# WIFI.net
KiCad netlist of a schematic drawn in Altium Designer
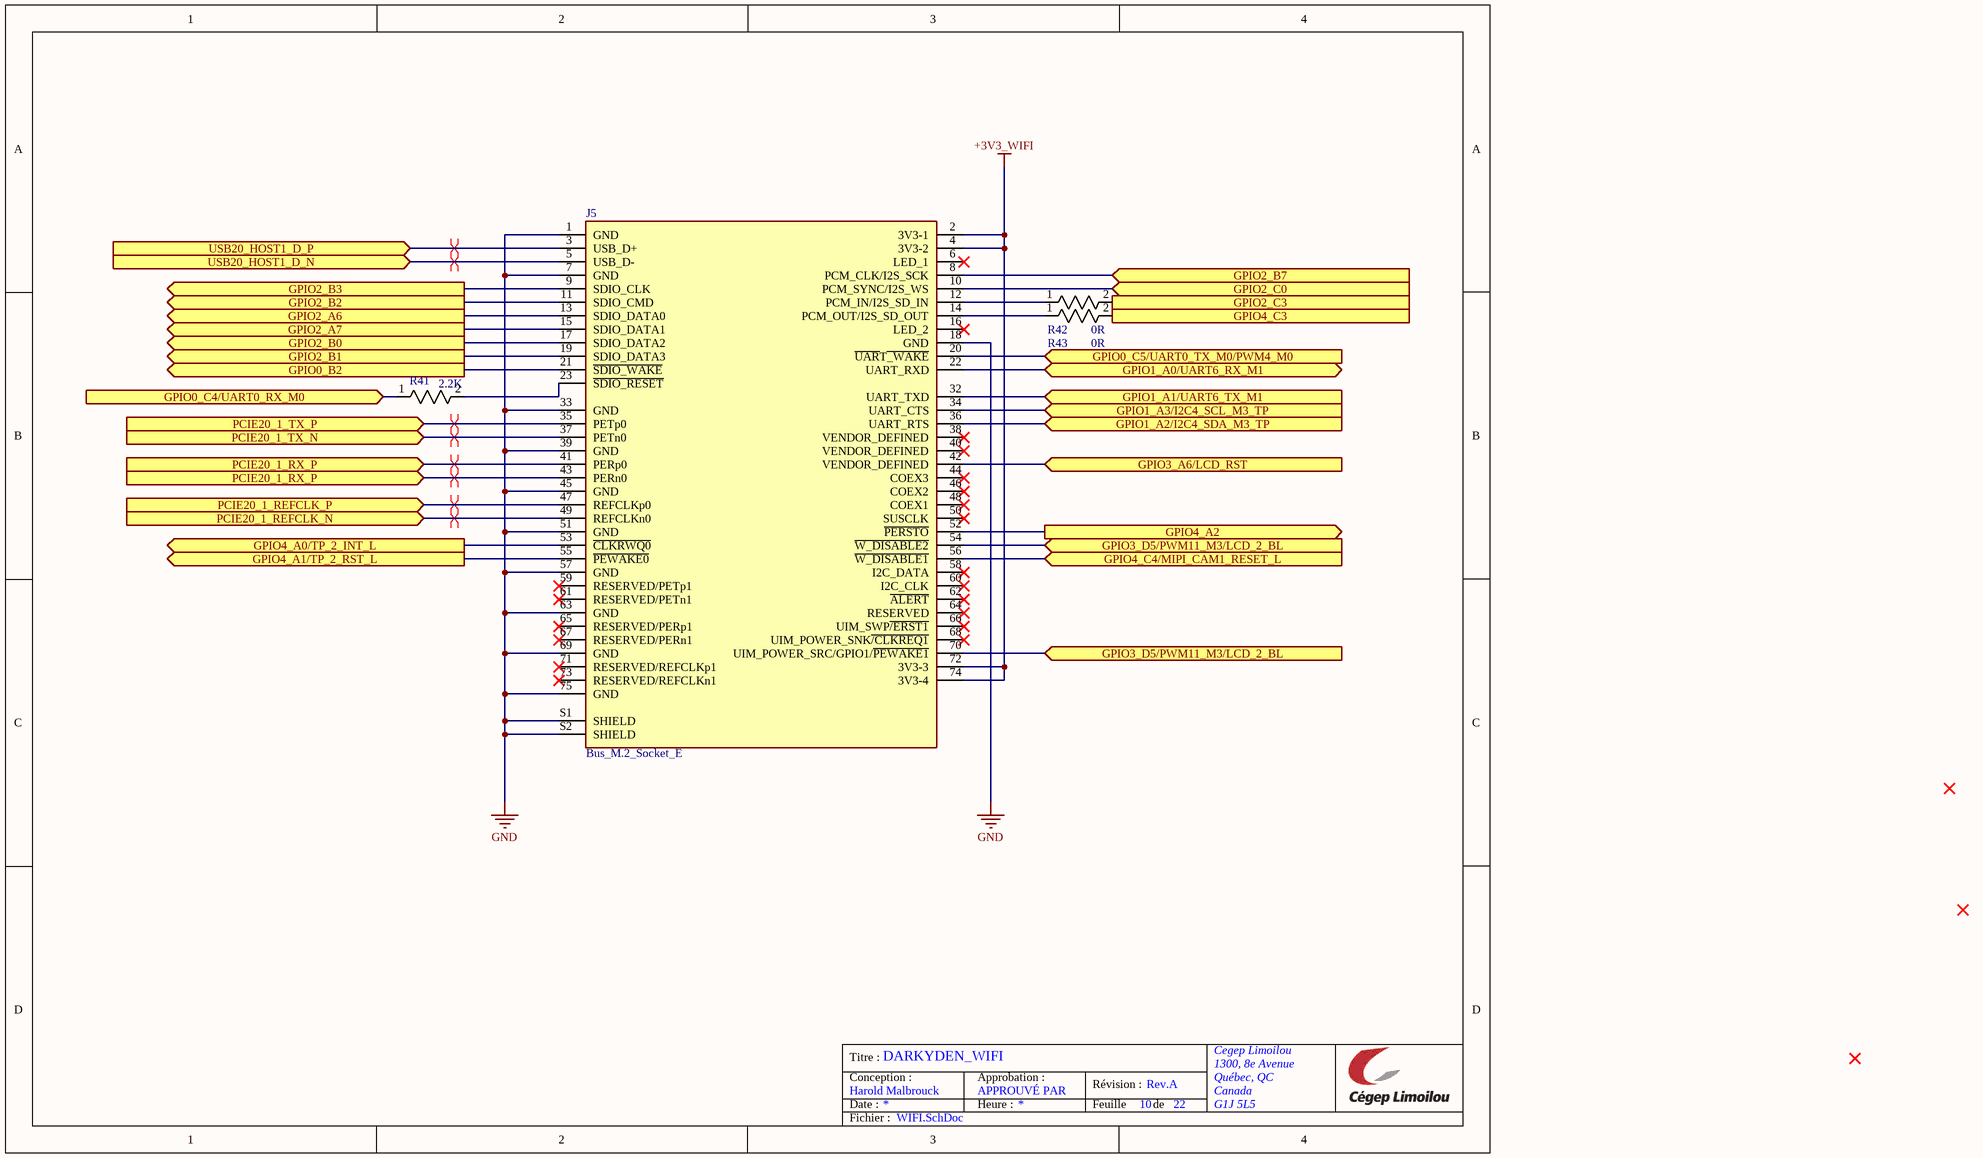
[diagram p0: WIFI.SchDoc]

(export (version "E")
  (design (tool "Eeschema 10.0.6"))
  (components
    (comp (ref "J5")
      (value "Bus_M.2_Socket_E")
      (footprint "AMPHENOL_MDT320E01001")
      (description "PCIe M.2 Connectors, Storage and Server Connector, P=0.5mm, H=3.2mm, Key E,30Î¼in Au Plating")
      (fields (field (name "MP") "MDT320E01001") (field (name "MF") "Amphenol ICC"))
      (libsource (lib "Bus_M.2_Socket_E") (part "Bus_M.2_Socket_E"))
    )
    (comp (ref "R41")
      (value "2.2K")
      (footprint "SamacSys:ERJ3EKF1000V")
      (description "2.2 kOhm, ï¿½ 5%, 100 mW, 0603 [1608 Metric], Thick Film, General Purpose")
      (fields
        (field (name "MANUFACTURER_PART_NUMBER") "ERJ-3GEYJ222V")
        (field (name "MOUSER PART NUMBER") "667-ERJ-3GEYJ222V")
      )
      (libsource (lib "SamacSys") (part "ERJ-3GEYJ222V"))
    )
    (comp (ref "R42")
      (value "0R")
      (footprint "SamacSys:ERJ3EKF1000V")
      (description "Zero Ohm Resistor, Jumper, 0603 [1608 Metric], Thick Film, 100 mW, 1 A, Surface Mount")
      (fields
        (field (name "MANUFACTURER_PART_NUMBER") "ERJ-3GEY0R00V")
        (field (name "MOUSER PART NUMBER") "667-ERJ-3GEY0R00V")
      )
      (libsource (lib "SamacSys") (part "ERJ-3GEY0R00V"))
    )
    (comp (ref "R43")
      (value "0R")
      (footprint "SamacSys:ERJ3EKF1000V")
      (description "Zero Ohm Resistor, Jumper, 0603 [1608 Metric], Thick Film, 100 mW, 1 A, Surface Mount")
      (fields
        (field (name "MANUFACTURER_PART_NUMBER") "ERJ-3GEY0R00V")
        (field (name "MOUSER PART NUMBER") "667-ERJ-3GEY0R00V")
      )
      (libsource (lib "SamacSys") (part "ERJ-3GEY0R00V"))
    )
  )
  (nets
    (net (code "1") (name "+3V3_WIFI") (class "Default")
      (node (ref "J5") (pin "2") (pinfunction "3V3-1_2") (pintype "power_in"))
      (node (ref "J5") (pin "4") (pinfunction "3V3-2_4") (pintype "power_in"))
      (node (ref "J5") (pin "72") (pinfunction "3V3-3_72") (pintype "power_in"))
      (node (ref "J5") (pin "74") (pinfunction "3V3-4_74") (pintype "power_in"))
    )
    (net (code "2") (name "/GPIO0_B2") (class "Default")
      (node (ref "J5") (pin "21") (pinfunction "~{SDIO_WAKE}_21") (pintype "passive"))
    )
    (net (code "3") (name "/GPIO0_C4{slash}UART0_RX_M0") (class "Default")
      (node (ref "R41") (pin "1") (pinfunction "1_1") (pintype "passive"))
    )
    (net (code "4") (name "/GPIO0_C5{slash}UART0_TX_M0{slash}PWM4_M0") (class "Default")
      (node (ref "J5") (pin "20") (pinfunction "~{UAR}T~{_WAKE}_20") (pintype "passive"))
    )
    (net (code "5") (name "/GPIO1_A0{slash}UART6_RX_M1") (class "Default")
      (node (ref "J5") (pin "22") (pinfunction "UART_RXD_22") (pintype "passive"))
    )
    (net (code "6") (name "/GPIO1_A1{slash}UART6_TX_M1") (class "Default")
      (node (ref "J5") (pin "32") (pinfunction "UART_TXD_32") (pintype "passive"))
    )
    (net (code "7") (name "/GPIO1_A2{slash}I2C4_SDA_M3_TP") (class "Default")
      (node (ref "J5") (pin "36") (pinfunction "UART_RTS_36") (pintype "passive"))
    )
    (net (code "8") (name "/GPIO1_A3{slash}I2C4_SCL_M3_TP") (class "Default")
      (node (ref "J5") (pin "34") (pinfunction "UART_CTS_34") (pintype "passive"))
    )
    (net (code "9") (name "/GPIO2_A6") (class "Default")
      (node (ref "J5") (pin "13") (pinfunction "SDIO_DATA0_13") (pintype "passive"))
    )
    (net (code "10") (name "/GPIO2_A7") (class "Default")
      (node (ref "J5") (pin "15") (pinfunction "SDIO_DATA1_15") (pintype "passive"))
    )
    (net (code "11") (name "/GPIO2_B0") (class "Default")
      (node (ref "J5") (pin "17") (pinfunction "SDIO_DATA2_17") (pintype "passive"))
    )
    (net (code "12") (name "/GPIO2_B1") (class "Default")
      (node (ref "J5") (pin "19") (pinfunction "SDIO_DATA3_19") (pintype "passive"))
    )
    (net (code "13") (name "/GPIO2_B2") (class "Default")
      (node (ref "J5") (pin "11") (pinfunction "SDIO_CMD_11") (pintype "passive"))
    )
    (net (code "14") (name "/GPIO2_B3") (class "Default")
      (node (ref "J5") (pin "9") (pinfunction "SDIO_CLK_9") (pintype "passive"))
    )
    (net (code "15") (name "/GPIO2_B7") (class "Default")
      (node (ref "J5") (pin "8") (pinfunction "PCM_CLK/I2S_SCK_8") (pintype "passive"))
    )
    (net (code "16") (name "/GPIO2_C0") (class "Default")
      (node (ref "J5") (pin "10") (pinfunction "PCM_SYNC/I2S_WS_10") (pintype "passive"))
    )
    (net (code "17") (name "/GPIO2_C3") (class "Default")
      (node (ref "R42") (pin "2") (pinfunction "2_2") (pintype "passive"))
    )
    (net (code "18") (name "/GPIO3_A6{slash}LCD_RST") (class "Default")
      (node (ref "J5") (pin "42") (pinfunction "VENDOR_DEFINED_42") (pintype "passive"))
    )
    (net (code "19") (name "/GPIO3_D5{slash}PWM11_M3{slash}LCD_2_BL") (class "Default")
      (node (ref "J5") (pin "54") (pinfunction "~{W_DISABLE2}_54") (pintype "passive"))
      (node (ref "J5") (pin "70") (pinfunction "UIM_POWER_SRC/GPIO1/~{PEWAKE1}_70") (pintype "passive"))
    )
    (net (code "20") (name "/GPIO4_A0{slash}TP_2_INT_L") (class "Default")
      (node (ref "J5") (pin "53") (pinfunction "~{CLKRWQ0}_53") (pintype "passive"))
    )
    (net (code "21") (name "/GPIO4_A1{slash}TP_2_RST_L") (class "Default")
      (node (ref "J5") (pin "55") (pinfunction "~{PEWAKE0}_55") (pintype "passive"))
    )
    (net (code "22") (name "/GPIO4_A2") (class "Default")
      (node (ref "J5") (pin "52") (pinfunction "~{PERSTO}_52") (pintype "passive"))
    )
    (net (code "23") (name "/GPIO4_C3") (class "Default")
      (node (ref "R43") (pin "2") (pinfunction "2_2") (pintype "passive"))
    )
    (net (code "24") (name "/GPIO4_C4{slash}MIPI_CAM1_RESET_L") (class "Default")
      (node (ref "J5") (pin "56") (pinfunction "~{W_DISABLE1}_56") (pintype "passive"))
    )
    (net (code "25") (name "/PCIE20_1_REFCLK_N") (class "Default")
      (node (ref "J5") (pin "49") (pinfunction "REFCLKn0_49") (pintype "passive"))
    )
    (net (code "26") (name "/PCIE20_1_REFCLK_P") (class "Default")
      (node (ref "J5") (pin "47") (pinfunction "REFCLKp0_47") (pintype "passive"))
    )
    (net (code "27") (name "/PCIE20_1_RX_P") (class "Default")
      (node (ref "J5") (pin "41") (pinfunction "PERp0_41") (pintype "passive"))
      (node (ref "J5") (pin "43") (pinfunction "PERn0_43") (pintype "passive"))
    )
    (net (code "28") (name "/PCIE20_1_TX_N") (class "Default")
      (node (ref "J5") (pin "37") (pinfunction "PETn0_37") (pintype "passive"))
    )
    (net (code "29") (name "/PCIE20_1_TX_P") (class "Default")
      (node (ref "J5") (pin "35") (pinfunction "PETp0_35") (pintype "passive"))
    )
    (net (code "30") (name "/USB20_HOST1_D_N") (class "Default")
      (node (ref "J5") (pin "5") (pinfunction "USB_D-_5") (pintype "passive"))
    )
    (net (code "31") (name "/USB20_HOST1_D_P") (class "Default")
      (node (ref "J5") (pin "3") (pinfunction "USB_D+_3") (pintype "passive"))
    )
    (net (code "32") (name "GND") (class "Default")
      (node (ref "J5") (pin "1") (pinfunction "GND_1") (pintype "passive"))
      (node (ref "J5") (pin "18") (pinfunction "GND_18") (pintype "passive"))
      (node (ref "J5") (pin "33") (pinfunction "GND_33") (pintype "passive"))
      (node (ref "J5") (pin "39") (pinfunction "GND_39") (pintype "passive"))
      (node (ref "J5") (pin "45") (pinfunction "GND_45") (pintype "passive"))
      (node (ref "J5") (pin "51") (pinfunction "GND_51") (pintype "passive"))
      (node (ref "J5") (pin "57") (pinfunction "GND_57") (pintype "passive"))
      (node (ref "J5") (pin "63") (pinfunction "GND_63") (pintype "passive"))
      (node (ref "J5") (pin "69") (pinfunction "GND_69") (pintype "passive"))
      (node (ref "J5") (pin "7") (pinfunction "GND_7") (pintype "passive"))
      (node (ref "J5") (pin "75") (pinfunction "GND_75") (pintype "passive"))
      (node (ref "J5") (pin "S1") (pinfunction "SHIELD_S1") (pintype "passive"))
      (node (ref "J5") (pin "S2") (pinfunction "SHIELD_S2") (pintype "passive"))
    )
    (net (code "33") (name "Net-(J5-PCM_IN{slash}I2S_SD_IN)") (class "Default")
      (node (ref "J5") (pin "12") (pinfunction "PCM_IN/I2S_SD_IN_12") (pintype "passive"))
      (node (ref "R42") (pin "1") (pinfunction "1_1") (pintype "passive"))
    )
    (net (code "34") (name "Net-(J5-PCM_OUT{slash}I2S_SD_OUT)") (class "Default")
      (node (ref "J5") (pin "14") (pinfunction "PCM_OUT/I2S_SD_OUT_14") (pintype "passive"))
      (node (ref "R43") (pin "1") (pinfunction "1_1") (pintype "passive"))
    )
    (net (code "35") (name "Net-(J5-~{SDIO_RESET})") (class "Default")
      (node (ref "J5") (pin "23") (pinfunction "~{SDIO_RESET}_23") (pintype "passive"))
      (node (ref "R41") (pin "2") (pinfunction "2_2") (pintype "passive"))
    )
    (net (code "36") (name "unconnected-(J5-COEX1-Pad48)") (class "Default")
      (node (ref "J5") (pin "48") (pinfunction "COEX1_48") (pintype "passive+no_connect"))
    )
    (net (code "37") (name "unconnected-(J5-COEX2-Pad46)") (class "Default")
      (node (ref "J5") (pin "46") (pinfunction "COEX2_46") (pintype "passive+no_connect"))
    )
    (net (code "38") (name "unconnected-(J5-COEX3-Pad44)") (class "Default")
      (node (ref "J5") (pin "44") (pinfunction "COEX3_44") (pintype "passive+no_connect"))
    )
    (net (code "39") (name "unconnected-(J5-I2C_CLK-Pad60)") (class "Default")
      (node (ref "J5") (pin "60") (pinfunction "I2C_CLK_60") (pintype "passive+no_connect"))
    )
    (net (code "40") (name "unconnected-(J5-I2C_DATA-Pad58)") (class "Default")
      (node (ref "J5") (pin "58") (pinfunction "I2C_DATA_58") (pintype "passive+no_connect"))
    )
    (net (code "41") (name "unconnected-(J5-LED_1-Pad6)") (class "Default")
      (node (ref "J5") (pin "6") (pinfunction "LED_1_6") (pintype "passive+no_connect"))
    )
    (net (code "42") (name "unconnected-(J5-LED_2-Pad16)") (class "Default")
      (node (ref "J5") (pin "16") (pinfunction "LED_2_16") (pintype "passive+no_connect"))
    )
    (net (code "43") (name "unconnected-(J5-RESERVED-Pad64)") (class "Default")
      (node (ref "J5") (pin "64") (pinfunction "RESERVED_64") (pintype "passive+no_connect"))
    )
    (net (code "44") (name "unconnected-(J5-RESERVED{slash}PERn1-Pad67)") (class "Default")
      (node (ref "J5") (pin "67") (pinfunction "RESERVED/PERn1_67") (pintype "passive+no_connect"))
    )
    (net (code "45") (name "unconnected-(J5-RESERVED{slash}PERp1-Pad65)") (class "Default")
      (node (ref "J5") (pin "65") (pinfunction "RESERVED/PERp1_65") (pintype "passive+no_connect"))
    )
    (net (code "46") (name "unconnected-(J5-RESERVED{slash}PETn1-Pad61)") (class "Default")
      (node (ref "J5") (pin "61") (pinfunction "RESERVED/PETn1_61") (pintype "passive+no_connect"))
    )
    (net (code "47") (name "unconnected-(J5-RESERVED{slash}PETp1-Pad59)") (class "Default")
      (node (ref "J5") (pin "59") (pinfunction "RESERVED/PETp1_59") (pintype "passive+no_connect"))
    )
    (net (code "48") (name "unconnected-(J5-RESERVED{slash}REFCLKn1-Pad73)") (class "Default")
      (node (ref "J5") (pin "73") (pinfunction "RESERVED/REFCLKn1_73") (pintype "passive+no_connect"))
    )
    (net (code "49") (name "unconnected-(J5-RESERVED{slash}REFCLKp1-Pad71)") (class "Default")
      (node (ref "J5") (pin "71") (pinfunction "RESERVED/REFCLKp1_71") (pintype "passive+no_connect"))
    )
    (net (code "50") (name "unconnected-(J5-SUSCLK-Pad50)") (class "Default")
      (node (ref "J5") (pin "50") (pinfunction "SUSCLK_50") (pintype "passive+no_connect"))
    )
    (net (code "51") (name "unconnected-(J5-UIM_POWER_SNK~{{slash}CLKREQ1}-Pad68)") (class "Default")
      (node (ref "J5") (pin "68") (pinfunction "UIM_POWER_SNK~{/CLKREQ1}_68") (pintype "passive+no_connect"))
    )
    (net (code "52") (name "unconnected-(J5-UIM_SWP~{{slash}ERST1}-Pad66)") (class "Default")
      (node (ref "J5") (pin "66") (pinfunction "UIM_SWP~{/ERST1}_66") (pintype "passive+no_connect"))
    )
    (net (code "53") (name "unconnected-(J5-VENDOR_DEFINED-Pad38)") (class "Default")
      (node (ref "J5") (pin "38") (pinfunction "VENDOR_DEFINED_38") (pintype "passive+no_connect"))
    )
    (net (code "54") (name "unconnected-(J5-VENDOR_DEFINED-Pad40)") (class "Default")
      (node (ref "J5") (pin "40") (pinfunction "VENDOR_DEFINED_40") (pintype "passive+no_connect"))
    )
    (net (code "55") (name "unconnected-(J5-~{ALERT}-Pad62)") (class "Default")
      (node (ref "J5") (pin "62") (pinfunction "~{ALERT}_62") (pintype "passive+no_connect"))
    )
  )
)
